# smd-proto.net
KiCad netlist of a schematic drawn in EAGLE
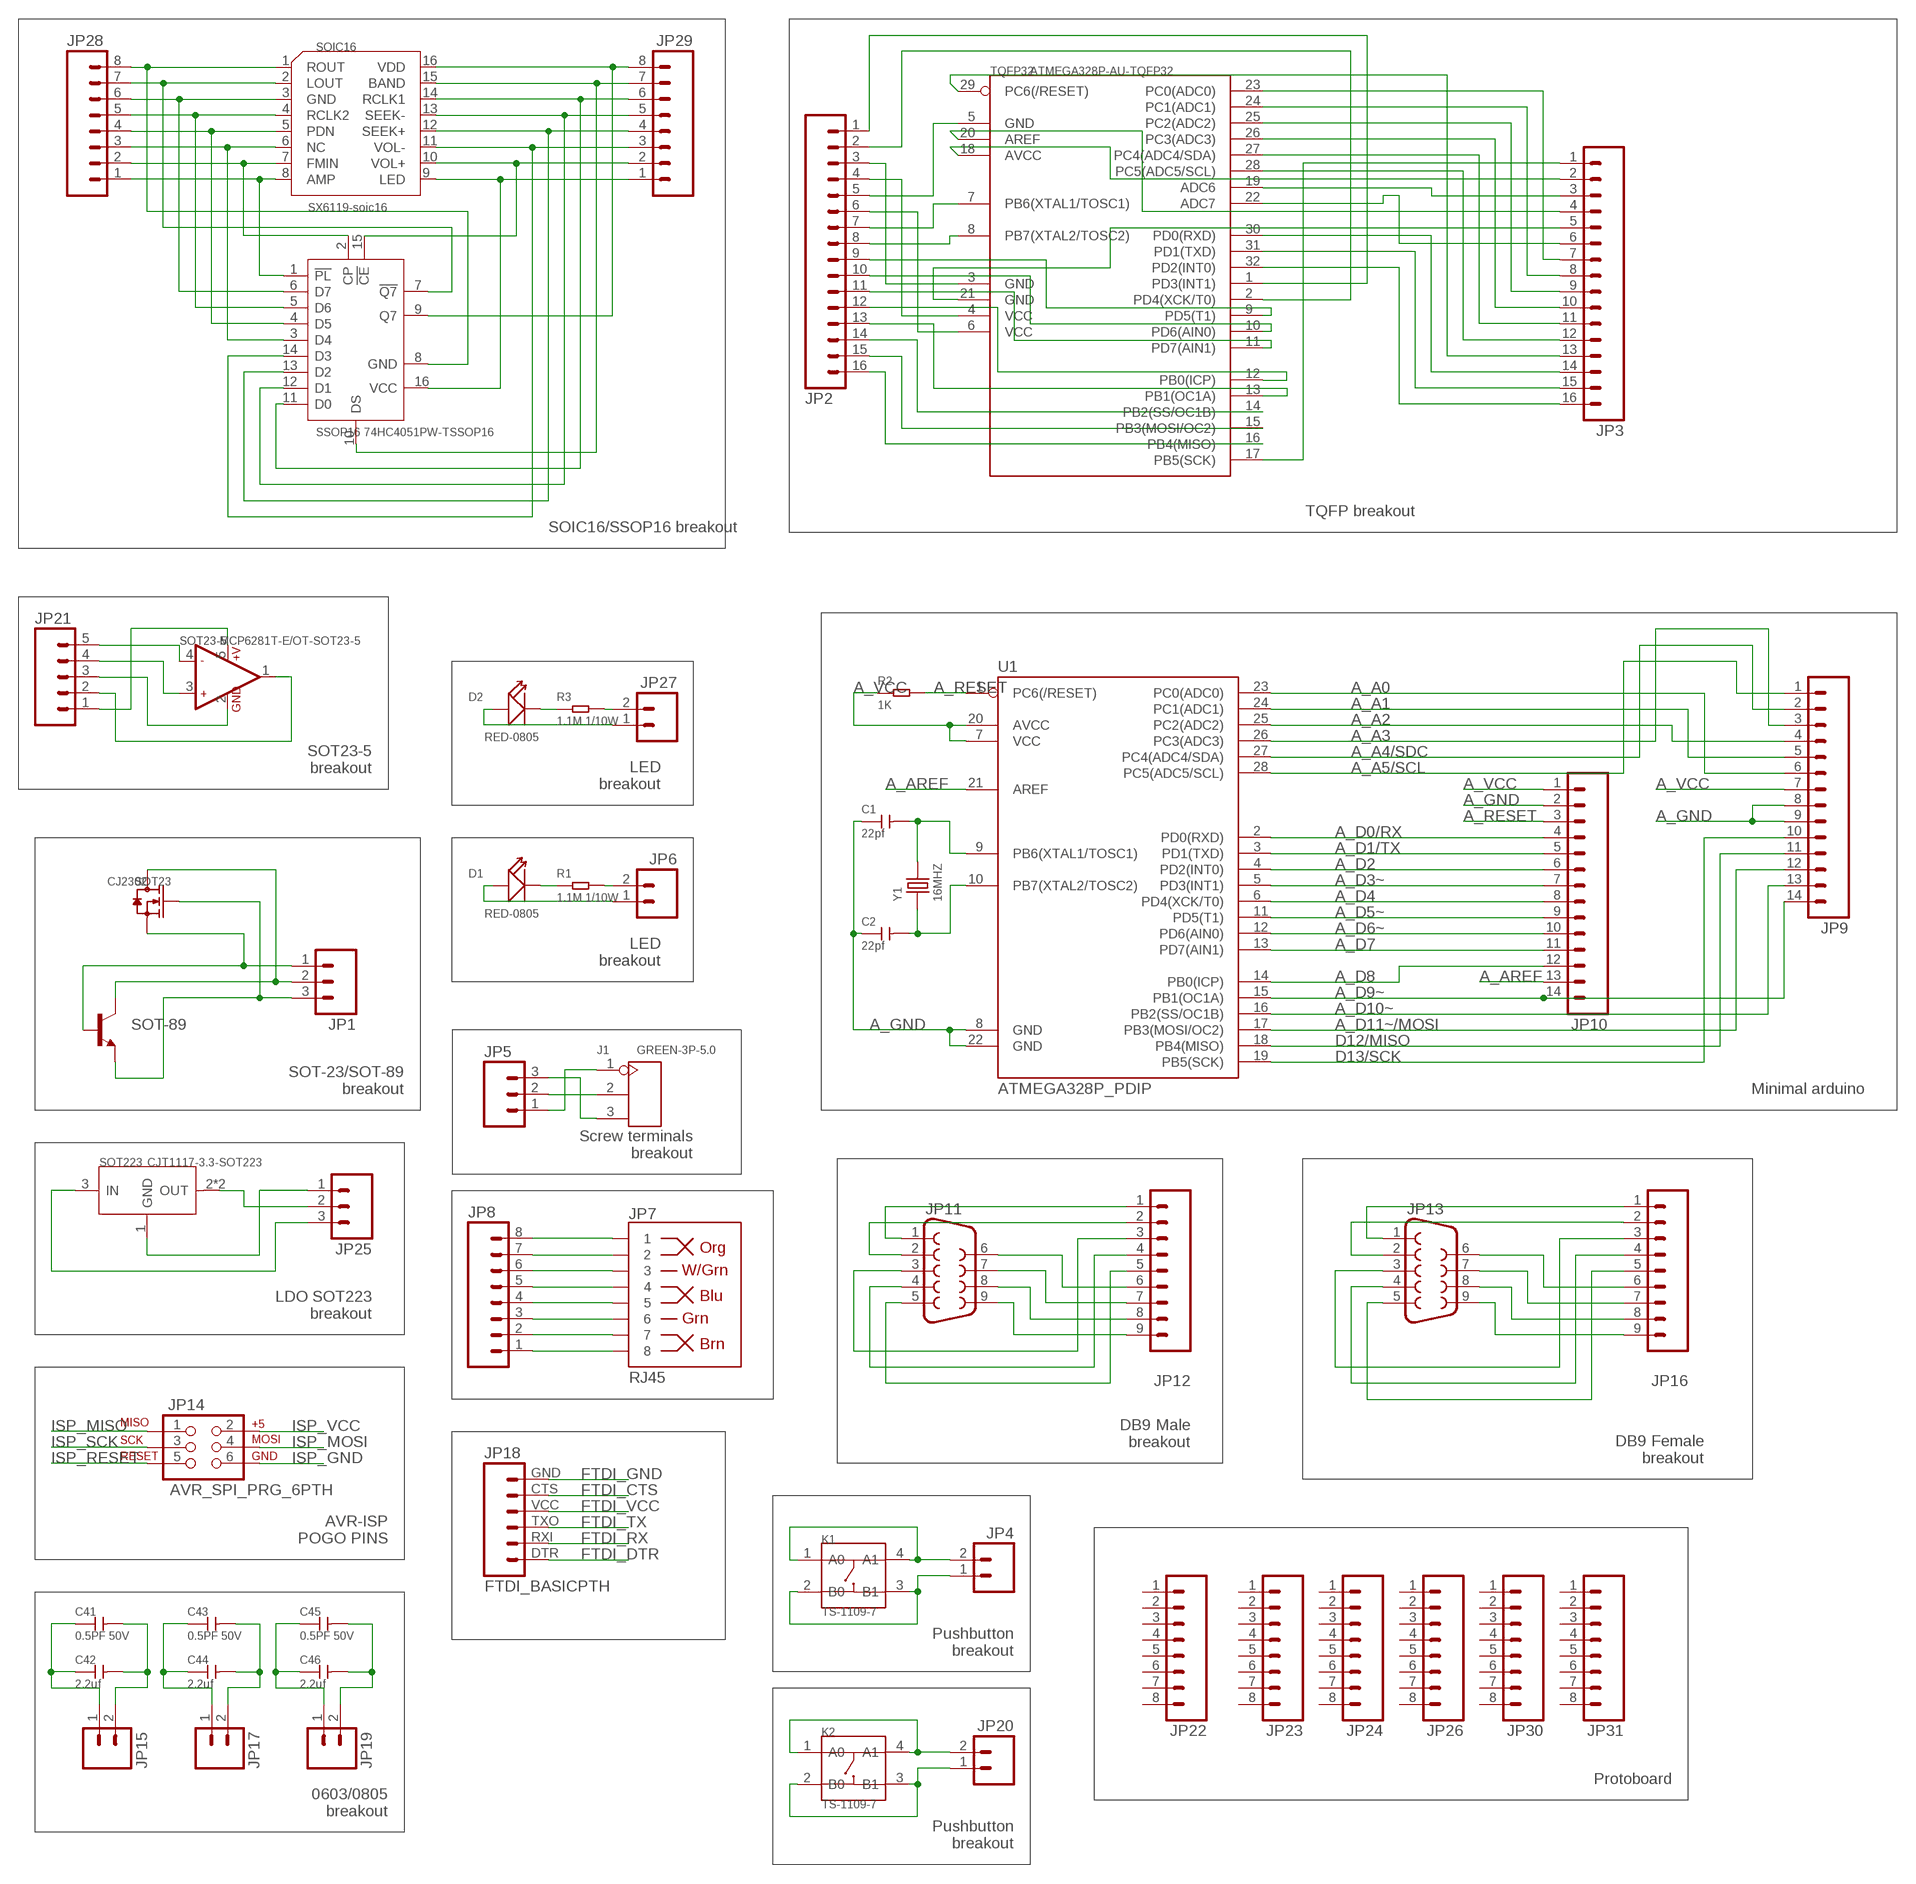
[diagram p0: schematic, sheet 1]

(export (version "E")
  (design (tool "Eeschema 10.0.6"))
  (components
    (comp (ref "C1")
      (value "22pf")
      (footprint "eagle-import:C0603")
      (libsource (lib "eagle-import") (part "CERAMIC-22PF-50V-5%-NPO(0603)"))
    )
    (comp (ref "C2")
      (value "22pf")
      (footprint "eagle-import:C0603")
      (libsource (lib "eagle-import") (part "CERAMIC-22PF-50V-5%-NPO(0603)"))
    )
    (comp (ref "C41")
      (value "0.5PF 50V")
      (footprint "eagle-import:C0603")
      (libsource (lib "eagle-import") (part "CERAMIC-0.5PF-50V-0.1PF-NPO(0603)"))
    )
    (comp (ref "C42")
      (value "2.2uf")
      (footprint "eagle-import:C0805")
      (fields (field (name "MPN") "CC0805KKX7R8BB225"))
      (libsource (lib "eagle-import") (part "CERAMIC-2.2UF-25V-10%-X7R(0805)"))
    )
    (comp (ref "C43")
      (value "0.5PF 50V")
      (footprint "eagle-import:C0603")
      (libsource (lib "eagle-import") (part "CERAMIC-0.5PF-50V-0.1PF-NPO(0603)"))
    )
    (comp (ref "C44")
      (value "2.2uf")
      (footprint "eagle-import:C0805")
      (fields (field (name "MPN") "CC0805KKX7R8BB225"))
      (libsource (lib "eagle-import") (part "CERAMIC-2.2UF-25V-10%-X7R(0805)"))
    )
    (comp (ref "C45")
      (value "0.5PF 50V")
      (footprint "eagle-import:C0603")
      (libsource (lib "eagle-import") (part "CERAMIC-0.5PF-50V-0.1PF-NPO(0603)"))
    )
    (comp (ref "C46")
      (value "2.2uf")
      (footprint "eagle-import:C0805")
      (fields (field (name "MPN") "CC0805KKX7R8BB225"))
      (libsource (lib "eagle-import") (part "CERAMIC-2.2UF-25V-10%-X7R(0805)"))
    )
    (comp (ref "D1")
      (value "RED-0805")
      (footprint "eagle-import:LED-0805")
      (fields (field (name "MPN") "17-215SURC/S530-A2/TR8"))
      (libsource (lib "eagle-import") (part "SMD-LED-CLEAR-RED(0805)"))
    )
    (comp (ref "D2")
      (value "RED-0805")
      (footprint "eagle-import:LED-0805")
      (fields (field (name "MPN") "17-215SURC/S530-A2/TR8"))
      (libsource (lib "eagle-import") (part "SMD-LED-CLEAR-RED(0805)"))
    )
    (comp (ref "J1")
      (value "GREEN-3P-5.0")
      (footprint "eagle-import:H3-5.0-15.5X8.0MM")
      (libsource (lib "eagle-import") (part "SCREW-TERMINAL-GREEN(3P-5.0)"))
    )
    (comp (ref "JP1")
      (value "M03PTH")
      (footprint "eagle-import:1X03")
      (libsource (lib "eagle-import") (part "M03PTH"))
    )
    (comp (ref "JP2")
      (value "M16PTH")
      (footprint "eagle-import:1X16")
      (libsource (lib "eagle-import") (part "M16PTH"))
    )
    (comp (ref "JP3")
      (value "M16PTH")
      (footprint "eagle-import:1X16")
      (libsource (lib "eagle-import") (part "M16PTH"))
    )
    (comp (ref "JP4")
      (value "M02PTH")
      (footprint "eagle-import:1X02")
      (libsource (lib "eagle-import") (part "M02PTH"))
    )
    (comp (ref "JP5")
      (value "M03PTH")
      (footprint "eagle-import:1X03")
      (libsource (lib "eagle-import") (part "M03PTH"))
    )
    (comp (ref "JP6")
      (value "M02PTH")
      (footprint "eagle-import:1X02")
      (libsource (lib "eagle-import") (part "M02PTH"))
    )
    (comp (ref "JP7")
      (value "RJ45")
      (footprint "eagle-import:RJ45-8")
      (libsource (lib "eagle-import") (part "RJ45-8PTH"))
    )
    (comp (ref "JP8")
      (value "M08")
      (footprint "eagle-import:1X08_ROUND")
      (libsource (lib "eagle-import") (part "M08"))
    )
    (comp (ref "JP9")
      (value "M14")
      (footprint "eagle-import:1X14")
      (libsource (lib "eagle-import") (part "M14"))
    )
    (comp (ref "JP10")
      (value "M14")
      (footprint "eagle-import:1X14")
      (libsource (lib "eagle-import") (part "M14"))
    )
    (comp (ref "JP11")
      (value "DB9MALE")
      (footprint "eagle-import:DB9_MALE")
      (libsource (lib "eagle-import") (part "DB9MALE"))
    )
    (comp (ref "JP12")
      (value "M09")
      (footprint "eagle-import:1X09")
      (libsource (lib "eagle-import") (part "M09"))
    )
    (comp (ref "JP13")
      (value "DB9FEMALE")
      (footprint "eagle-import:DB9")
      (libsource (lib "eagle-import") (part "DB9FEMALE"))
    )
    (comp (ref "JP14")
      (value "AVR_SPI_PRG_6PTH")
      (footprint "eagle-import:2X3")
      (libsource (lib "eagle-import") (part "AVR_SPI_PRG_6PTH"))
    )
    (comp (ref "JP15")
      (value "M02PTH")
      (footprint "eagle-import:1X02")
      (libsource (lib "eagle-import") (part "M02PTH"))
    )
    (comp (ref "JP16")
      (value "M09")
      (footprint "eagle-import:1X09")
      (libsource (lib "eagle-import") (part "M09"))
    )
    (comp (ref "JP17")
      (value "M02PTH")
      (footprint "eagle-import:1X02")
      (libsource (lib "eagle-import") (part "M02PTH"))
    )
    (comp (ref "JP18")
      (value "FTDI_BASICPTH")
      (footprint "eagle-import:FTDI_BASIC")
      (libsource (lib "eagle-import") (part "FTDI_BASICPTH"))
    )
    (comp (ref "JP19")
      (value "M02PTH")
      (footprint "eagle-import:1X02")
      (libsource (lib "eagle-import") (part "M02PTH"))
    )
    (comp (ref "JP20")
      (value "M02PTH")
      (footprint "eagle-import:1X02")
      (libsource (lib "eagle-import") (part "M02PTH"))
    )
    (comp (ref "JP21")
      (value "M05PTH")
      (footprint "eagle-import:1X05")
      (libsource (lib "eagle-import") (part "M05PTH"))
    )
    (comp (ref "JP22")
      (value "M08NO_SILK_FEMALE_PTH")
      (footprint "eagle-import:1X08_NO_SILK")
      (libsource (lib "eagle-import") (part "M08NO_SILK_FEMALE_PTH"))
    )
    (comp (ref "JP23")
      (value "M08NO_SILK_FEMALE_PTH")
      (footprint "eagle-import:1X08_NO_SILK")
      (libsource (lib "eagle-import") (part "M08NO_SILK_FEMALE_PTH"))
    )
    (comp (ref "JP24")
      (value "M08NO_SILK_FEMALE_PTH")
      (footprint "eagle-import:1X08_NO_SILK")
      (libsource (lib "eagle-import") (part "M08NO_SILK_FEMALE_PTH"))
    )
    (comp (ref "JP25")
      (value "M03PTH")
      (footprint "eagle-import:1X03")
      (libsource (lib "eagle-import") (part "M03PTH"))
    )
    (comp (ref "JP26")
      (value "M08NO_SILK_FEMALE_PTH")
      (footprint "eagle-import:1X08_NO_SILK")
      (libsource (lib "eagle-import") (part "M08NO_SILK_FEMALE_PTH"))
    )
    (comp (ref "JP27")
      (value "M02PTH")
      (footprint "eagle-import:1X02")
      (libsource (lib "eagle-import") (part "M02PTH"))
    )
    (comp (ref "JP28")
      (value "M08")
      (footprint "eagle-import:1X08_ROUND")
      (libsource (lib "eagle-import") (part "M08"))
    )
    (comp (ref "JP29")
      (value "M08")
      (footprint "eagle-import:1X08_ROUND")
      (libsource (lib "eagle-import") (part "M08"))
    )
    (comp (ref "JP30")
      (value "M08NO_SILK_FEMALE_PTH")
      (footprint "eagle-import:1X08_NO_SILK")
      (libsource (lib "eagle-import") (part "M08NO_SILK_FEMALE_PTH"))
    )
    (comp (ref "JP31")
      (value "M08NO_SILK_FEMALE_PTH")
      (footprint "eagle-import:1X08_NO_SILK")
      (libsource (lib "eagle-import") (part "M08NO_SILK_FEMALE_PTH"))
    )
    (comp (ref "K1")
      (value "TS-1109-7")
      (footprint "eagle-import:SW4-6.2X6.2X5.0MM")
      (libsource (lib "eagle-import") (part "DIP-BUTTON-TOP-BLACK(4P-D6.2MM)"))
    )
    (comp (ref "K2")
      (value "TS-1109-7")
      (footprint "eagle-import:SW4-6.2X6.2X5.0MM")
      (libsource (lib "eagle-import") (part "DIP-BUTTON-TOP-BLACK(4P-D6.2MM)"))
    )
    (comp (ref "R1")
      (value "1.1M 1/10W")
      (footprint "eagle-import:R0603")
      (fields (field (name "MPN") "RC0603FR-071M1L"))
      (libsource (lib "eagle-import") (part "SMD-RES-1.1M-1%-1/10W(0603)"))
    )
    (comp (ref "R2")
      (value "1K")
      (footprint "eagle-import:R0603")
      (fields (field (name "MPN") "RC0603JR-075K6L"))
      (libsource (lib "eagle-import") (part "SMD-RES-5.6K-5%-1/10W(0603)"))
    )
    (comp (ref "R3")
      (value "1.1M 1/10W")
      (footprint "eagle-import:R0603")
      (fields (field (name "MPN") "RC0603FR-071M1L"))
      (libsource (lib "eagle-import") (part "SMD-RES-1.1M-1%-1/10W(0603)"))
    )
    (comp (ref "SOIC16")
      (value "SX6119-soic16")
      (footprint "eagle-import:SOIC16-1.27-10X3.9MM")
      (fields (field (name "MPN") "SX6119"))
      (libsource (lib "eagle-import") (part "AMPLIFIER-SX6119(SOIC16)"))
    )
    (comp (ref "SOT-89")
      (value "TRANSISTOR_NPNSOT89")
      (footprint "eagle-import:SOT89")
      (libsource (lib "eagle-import") (part "TRANSISTOR_NPNSOT89"))
    )
    (comp (ref "SOT23")
      (value "CJ2302")
      (footprint "eagle-import:SOT-23")
      (libsource (lib "eagle-import") (part "SMD-MOSFET-N-CH-20V-2.1A-CJ2302(SOT-23)"))
    )
    (comp (ref "SOT23-5")
      (value "MCP6281T-E/OT-SOT23-5")
      (footprint "eagle-import:SOT-23-5")
      (fields (field (name "MPN") "MCP6281T-E/OT"))
      (libsource (lib "eagle-import") (part "AMPLIFIER-MCP6281T-E/OT(SOT23-5)"))
    )
    (comp (ref "SOT223")
      (value "CJT1117-3.3-SOT223")
      (footprint "eagle-import:SOT-223")
      (fields (field (name "MPN") "CJT1117-3.3"))
      (libsource (lib "eagle-import") (part "PMIC-CJT1117-3.3(SOT223)"))
    )
    (comp (ref "SSOP16")
      (value "74HC4051PW-TSSOP16")
      (footprint "eagle-import:TSSOP16-0.65-5X4.4MM")
      (fields (field (name "MPN") "74HC4051PW"))
      (libsource (lib "eagle-import") (part "LOGIC-74HC4051PW(TSSOP16)"))
    )
    (comp (ref "TQFP32")
      (value "ATMEGA328P-AU-TQFP32")
      (footprint "eagle-import:TQFP32-0.8-7X7MM")
      (fields (field (name "MPN") "ATMEGA328P-AU"))
      (libsource (lib "eagle-import") (part "MCU-ATMEGA328P-AU(TQFP32)"))
    )
    (comp (ref "U1")
      (value "ATMEGA328P_PDIP")
      (footprint "eagle-import:DIL28-3")
      (libsource (lib "eagle-import") (part "ATMEGA328P_PDIP"))
    )
    (comp (ref "Y1")
      (value "16MHZ")
      (footprint "eagle-import:X2-SMD-5.0X3.2X1.3MM")
      (fields (field (name "MPN") "X053201602002"))
      (libsource (lib "eagle-import") (part "SMD-CRYSTAL-16MHZ-8PF-20PPM-40R(2P-5.0X3.2MM)"))
    )
  )
  (nets
    (net (code "1") (name "/A_A0") (class "Default")
      (node (ref "JP9") (pin "6") (pinfunction "6_6") (pintype "passive"))
      (node (ref "U1") (pin "23") (pinfunction "PC0(ADC0)_23") (pintype "bidirectional"))
    )
    (net (code "2") (name "/A_A1") (class "Default")
      (node (ref "JP9") (pin "5") (pinfunction "5_5") (pintype "passive"))
      (node (ref "U1") (pin "24") (pinfunction "PC1(ADC1)_24") (pintype "bidirectional"))
    )
    (net (code "3") (name "/A_A2") (class "Default")
      (node (ref "JP9") (pin "4") (pinfunction "4_4") (pintype "passive"))
      (node (ref "U1") (pin "25") (pinfunction "PC2(ADC2)_25") (pintype "bidirectional"))
    )
    (net (code "4") (name "/A_A3") (class "Default")
      (node (ref "JP9") (pin "3") (pinfunction "3_3") (pintype "passive"))
      (node (ref "U1") (pin "26") (pinfunction "PC3(ADC3)_26") (pintype "bidirectional"))
    )
    (net (code "5") (name "/A_A4{slash}SDC") (class "Default")
      (node (ref "JP9") (pin "2") (pinfunction "2_2") (pintype "passive"))
      (node (ref "U1") (pin "27") (pinfunction "PC4(ADC4/SDA)_27") (pintype "bidirectional"))
    )
    (net (code "6") (name "/A_A5{slash}SCL") (class "Default")
      (node (ref "JP9") (pin "1") (pinfunction "1_1") (pintype "passive"))
      (node (ref "U1") (pin "28") (pinfunction "PC5(ADC5/SCL)_28") (pintype "bidirectional"))
    )
    (net (code "7") (name "/A_AREF") (class "Default")
      (node (ref "JP10") (pin "13") (pinfunction "13_13") (pintype "passive"))
      (node (ref "U1") (pin "21") (pinfunction "AREF_21") (pintype "bidirectional"))
    )
    (net (code "8") (name "/A_D0{slash}RX") (class "Default")
      (node (ref "JP10") (pin "4") (pinfunction "4_4") (pintype "passive"))
      (node (ref "U1") (pin "2") (pinfunction "PD0(RXD)_2") (pintype "bidirectional"))
    )
    (net (code "9") (name "/A_D1{slash}TX") (class "Default")
      (node (ref "JP10") (pin "5") (pinfunction "5_5") (pintype "passive"))
      (node (ref "U1") (pin "3") (pinfunction "PD1(TXD)_3") (pintype "bidirectional"))
    )
    (net (code "10") (name "/A_D2") (class "Default")
      (node (ref "JP10") (pin "6") (pinfunction "6_6") (pintype "passive"))
      (node (ref "U1") (pin "4") (pinfunction "PD2(INT0)_4") (pintype "bidirectional"))
    )
    (net (code "11") (name "/A_D3~{}") (class "Default")
      (node (ref "JP10") (pin "7") (pinfunction "7_7") (pintype "passive"))
      (node (ref "U1") (pin "5") (pinfunction "PD3(INT1)_5") (pintype "bidirectional"))
    )
    (net (code "12") (name "/A_D4") (class "Default")
      (node (ref "JP10") (pin "8") (pinfunction "8_8") (pintype "passive"))
      (node (ref "U1") (pin "6") (pinfunction "PD4(XCK/T0)_6") (pintype "bidirectional"))
    )
    (net (code "13") (name "/A_D5~{}") (class "Default")
      (node (ref "JP10") (pin "9") (pinfunction "9_9") (pintype "passive"))
      (node (ref "U1") (pin "11") (pinfunction "PD5(T1)_11") (pintype "bidirectional"))
    )
    (net (code "14") (name "/A_D6~{}") (class "Default")
      (node (ref "JP10") (pin "10") (pinfunction "10_10") (pintype "passive"))
      (node (ref "U1") (pin "12") (pinfunction "PD6(AIN0)_12") (pintype "bidirectional"))
    )
    (net (code "15") (name "/A_D7") (class "Default")
      (node (ref "JP10") (pin "11") (pinfunction "11_11") (pintype "passive"))
      (node (ref "U1") (pin "13") (pinfunction "PD7(AIN1)_13") (pintype "bidirectional"))
    )
    (net (code "16") (name "/A_D8") (class "Default")
      (node (ref "JP10") (pin "12") (pinfunction "12_12") (pintype "passive"))
      (node (ref "U1") (pin "14") (pinfunction "PB0(ICP)_14") (pintype "bidirectional"))
    )
    (net (code "17") (name "/A_D9~{}") (class "Default")
      (node (ref "JP10") (pin "14") (pinfunction "14_14") (pintype "passive"))
      (node (ref "JP9") (pin "14") (pinfunction "14_14") (pintype "passive"))
      (node (ref "U1") (pin "15") (pinfunction "PB1(OC1A)_15") (pintype "bidirectional"))
    )
    (net (code "18") (name "/A_D10~{}") (class "Default")
      (node (ref "JP9") (pin "13") (pinfunction "13_13") (pintype "passive"))
      (node (ref "U1") (pin "16") (pinfunction "PB2(SS/OC1B)_16") (pintype "bidirectional"))
    )
    (net (code "19") (name "/A_D11~{{slash}MOSI}") (class "Default")
      (node (ref "JP9") (pin "12") (pinfunction "12_12") (pintype "passive"))
      (node (ref "U1") (pin "17") (pinfunction "PB3(MOSI/OC2)_17") (pintype "bidirectional"))
    )
    (net (code "20") (name "/A_GND") (class "Default")
      (node (ref "C1") (pin "1") (pinfunction "1_1") (pintype "passive"))
      (node (ref "C2") (pin "1") (pinfunction "1_1") (pintype "passive"))
      (node (ref "JP10") (pin "2") (pinfunction "2_2") (pintype "passive"))
      (node (ref "JP9") (pin "8") (pinfunction "8_8") (pintype "passive"))
      (node (ref "JP9") (pin "9") (pinfunction "9_9") (pintype "passive"))
      (node (ref "U1") (pin "22") (pinfunction "GND_22") (pintype "bidirectional"))
      (node (ref "U1") (pin "8") (pinfunction "GND_8") (pintype "bidirectional"))
    )
    (net (code "21") (name "/A_RESET") (class "Default")
      (node (ref "JP10") (pin "3") (pinfunction "3_3") (pintype "passive"))
      (node (ref "R2") (pin "2") (pinfunction "2_2") (pintype "passive"))
      (node (ref "U1") (pin "1") (pinfunction "PC6(/RESET)_1") (pintype "bidirectional"))
    )
    (net (code "22") (name "/A_VCC") (class "Default")
      (node (ref "JP10") (pin "1") (pinfunction "1_1") (pintype "passive"))
      (node (ref "JP9") (pin "7") (pinfunction "7_7") (pintype "passive"))
      (node (ref "R2") (pin "1") (pinfunction "1_1") (pintype "passive"))
      (node (ref "U1") (pin "20") (pinfunction "AVCC_20") (pintype "bidirectional"))
      (node (ref "U1") (pin "7") (pinfunction "VCC_7") (pintype "bidirectional"))
    )
    (net (code "23") (name "/D12{slash}MISO") (class "Default")
      (node (ref "JP9") (pin "11") (pinfunction "11_11") (pintype "passive"))
      (node (ref "U1") (pin "18") (pinfunction "PB4(MISO)_18") (pintype "bidirectional"))
    )
    (net (code "24") (name "/D13{slash}SCK") (class "Default")
      (node (ref "JP9") (pin "10") (pinfunction "10_10") (pintype "passive"))
      (node (ref "U1") (pin "19") (pinfunction "PB5(SCK)_19") (pintype "bidirectional"))
    )
    (net (code "25") (name "/FTDI_CTS") (class "Default")
      (node (ref "JP18") (pin "CTS") (pinfunction "5_CTS") (pintype "passive"))
    )
    (net (code "26") (name "/FTDI_DTR") (class "Default")
      (node (ref "JP18") (pin "DTR") (pinfunction "1_DTR") (pintype "passive"))
    )
    (net (code "27") (name "/FTDI_GND") (class "Default")
      (node (ref "JP18") (pin "GND") (pinfunction "6_GND") (pintype "passive"))
    )
    (net (code "28") (name "/FTDI_RX") (class "Default")
      (node (ref "JP18") (pin "RXI") (pinfunction "2_RXI") (pintype "passive"))
    )
    (net (code "29") (name "/FTDI_TX") (class "Default")
      (node (ref "JP18") (pin "TXO") (pinfunction "3_TXO") (pintype "passive"))
    )
    (net (code "30") (name "/FTDI_VCC") (class "Default")
      (node (ref "JP18") (pin "VCC") (pinfunction "4_VCC") (pintype "passive"))
    )
    (net (code "31") (name "/ISP_GND") (class "Default")
      (node (ref "JP14") (pin "6") (pinfunction "6_6") (pintype "passive"))
    )
    (net (code "32") (name "/ISP_MISO") (class "Default")
      (node (ref "JP14") (pin "1") (pinfunction "1_1") (pintype "passive"))
    )
    (net (code "33") (name "/ISP_MOSI") (class "Default")
      (node (ref "JP14") (pin "4") (pinfunction "4_4") (pintype "passive"))
    )
    (net (code "34") (name "/ISP_RESET") (class "Default")
      (node (ref "JP14") (pin "5") (pinfunction "5_5") (pintype "passive"))
    )
    (net (code "35") (name "/ISP_SCK") (class "Default")
      (node (ref "JP14") (pin "3") (pinfunction "3_3") (pintype "passive"))
    )
    (net (code "36") (name "/ISP_VCC") (class "Default")
      (node (ref "JP14") (pin "2") (pinfunction "2_2") (pintype "passive"))
    )
    (net (code "37") (name "Net-(C41-Pad1)") (class "Default")
      (node (ref "C41") (pin "1") (pinfunction "1_1") (pintype "passive"))
      (node (ref "C42") (pin "1") (pinfunction "1_1") (pintype "passive"))
      (node (ref "JP15") (pin "1") (pinfunction "1_1") (pintype "passive"))
    )
    (net (code "38") (name "Net-(C41-Pad2)") (class "Default")
      (node (ref "C41") (pin "2") (pinfunction "2_2") (pintype "passive"))
      (node (ref "C42") (pin "2") (pinfunction "2_2") (pintype "passive"))
      (node (ref "JP15") (pin "2") (pinfunction "2_2") (pintype "passive"))
    )
    (net (code "39") (name "Net-(C43-Pad1)") (class "Default")
      (node (ref "C43") (pin "1") (pinfunction "1_1") (pintype "passive"))
      (node (ref "C44") (pin "1") (pinfunction "1_1") (pintype "passive"))
      (node (ref "JP17") (pin "1") (pinfunction "1_1") (pintype "passive"))
    )
    (net (code "40") (name "Net-(C43-Pad2)") (class "Default")
      (node (ref "C43") (pin "2") (pinfunction "2_2") (pintype "passive"))
      (node (ref "C44") (pin "2") (pinfunction "2_2") (pintype "passive"))
      (node (ref "JP17") (pin "2") (pinfunction "2_2") (pintype "passive"))
    )
    (net (code "41") (name "Net-(C45-Pad1)") (class "Default")
      (node (ref "C45") (pin "1") (pinfunction "1_1") (pintype "passive"))
      (node (ref "C46") (pin "1") (pinfunction "1_1") (pintype "passive"))
      (node (ref "JP19") (pin "1") (pinfunction "1_1") (pintype "passive"))
    )
    (net (code "42") (name "Net-(C45-Pad2)") (class "Default")
      (node (ref "C45") (pin "2") (pinfunction "2_2") (pintype "passive"))
      (node (ref "C46") (pin "2") (pinfunction "2_2") (pintype "passive"))
      (node (ref "JP19") (pin "2") (pinfunction "2_2") (pintype "passive"))
    )
    (net (code "43") (name "Net-(D1-Pad+)") (class "Default")
      (node (ref "D1") (pin "+") (pinfunction "+_+") (pintype "passive"))
      (node (ref "JP6") (pin "1") (pinfunction "1_1") (pintype "passive"))
    )
    (net (code "44") (name "Net-(D1-Pad-)") (class "Default")
      (node (ref "D1") (pin "-") (pinfunction "-_-") (pintype "passive"))
      (node (ref "R1") (pin "1") (pinfunction "1_1") (pintype "passive"))
    )
    (net (code "45") (name "Net-(D2-Pad+)") (class "Default")
      (node (ref "D2") (pin "+") (pinfunction "+_+") (pintype "passive"))
      (node (ref "JP27") (pin "1") (pinfunction "1_1") (pintype "passive"))
    )
    (net (code "46") (name "Net-(D2-Pad-)") (class "Default")
      (node (ref "D2") (pin "-") (pinfunction "-_-") (pintype "passive"))
      (node (ref "R3") (pin "1") (pinfunction "1_1") (pintype "passive"))
    )
    (net (code "47") (name "Net-(J1-P$1)") (class "Default")
      (node (ref "J1") (pin "1") (pinfunction "P$1_1") (pintype "bidirectional"))
      (node (ref "JP5") (pin "1") (pinfunction "1_1") (pintype "passive"))
    )
    (net (code "48") (name "Net-(J1-P$2)") (class "Default")
      (node (ref "J1") (pin "2") (pinfunction "P$2_2") (pintype "bidirectional"))
      (node (ref "JP5") (pin "2") (pinfunction "2_2") (pintype "passive"))
    )
    (net (code "49") (name "Net-(J1-P$3)") (class "Default")
      (node (ref "J1") (pin "3") (pinfunction "P$3_3") (pintype "bidirectional"))
      (node (ref "JP5") (pin "3") (pinfunction "3_3") (pintype "passive"))
    )
    (net (code "50") (name "Net-(JP2-Pad3)") (class "Default")
      (node (ref "JP2") (pin "3") (pinfunction "3_3") (pintype "passive"))
      (node (ref "TQFP32") (pin "3") (pinfunction "GND_3") (pintype "bidirectional"))
    )
    (net (code "51") (name "Net-(JP2-Pad4)") (class "Default")
      (node (ref "JP2") (pin "4") (pinfunction "4_4") (pintype "passive"))
      (node (ref "TQFP32") (pin "4") (pinfunction "VCC_4") (pintype "bidirectional"))
    )
    (net (code "52") (name "Net-(JP2-Pad5)") (class "Default")
      (node (ref "JP2") (pin "5") (pinfunction "5_5") (pintype "passive"))
      (node (ref "TQFP32") (pin "5") (pinfunction "GND_5") (pintype "bidirectional"))
    )
    (net (code "53") (name "Net-(JP2-Pad6)") (class "Default")
      (node (ref "JP2") (pin "6") (pinfunction "6_6") (pintype "passive"))
      (node (ref "TQFP32") (pin "6") (pinfunction "VCC_6") (pintype "bidirectional"))
    )
    (net (code "54") (name "Net-(JP3-Pad5)") (class "Default")
      (node (ref "JP3") (pin "5") (pinfunction "5_5") (pintype "passive"))
      (node (ref "TQFP32") (pin "21") (pinfunction "GND_21") (pintype "bidirectional"))
    )
    (net (code "55") (name "Net-(JP6-Pad2)") (class "Default")
      (node (ref "JP6") (pin "2") (pinfunction "2_2") (pintype "passive"))
      (node (ref "R1") (pin "2") (pinfunction "2_2") (pintype "passive"))
    )
    (net (code "56") (name "Net-(JP7-Pad1)") (class "Default")
      (node (ref "JP7") (pin "1") (pinfunction "1_1") (pintype "bidirectional"))
      (node (ref "JP8") (pin "8") (pinfunction "8_8") (pintype "passive"))
    )
    (net (code "57") (name "Net-(JP7-Pad2)") (class "Default")
      (node (ref "JP7") (pin "2") (pinfunction "2_2") (pintype "bidirectional"))
      (node (ref "JP8") (pin "7") (pinfunction "7_7") (pintype "passive"))
    )
    (net (code "58") (name "Net-(JP7-Pad3)") (class "Default")
      (node (ref "JP7") (pin "3") (pinfunction "3_3") (pintype "bidirectional"))
      (node (ref "JP8") (pin "6") (pinfunction "6_6") (pintype "passive"))
    )
    (net (code "59") (name "Net-(JP7-Pad4)") (class "Default")
      (node (ref "JP7") (pin "4") (pinfunction "4_4") (pintype "bidirectional"))
      (node (ref "JP8") (pin "5") (pinfunction "5_5") (pintype "passive"))
    )
    (net (code "60") (name "Net-(JP7-Pad5)") (class "Default")
      (node (ref "JP7") (pin "5") (pinfunction "5_5") (pintype "bidirectional"))
      (node (ref "JP8") (pin "4") (pinfunction "4_4") (pintype "passive"))
    )
    (net (code "61") (name "Net-(JP7-Pad6)") (class "Default")
      (node (ref "JP7") (pin "6") (pinfunction "6_6") (pintype "bidirectional"))
      (node (ref "JP8") (pin "3") (pinfunction "3_3") (pintype "passive"))
    )
    (net (code "62") (name "Net-(JP7-Pad7)") (class "Default")
      (node (ref "JP7") (pin "7") (pinfunction "7_7") (pintype "bidirectional"))
      (node (ref "JP8") (pin "2") (pinfunction "2_2") (pintype "passive"))
    )
    (net (code "63") (name "Net-(JP7-Pad8)") (class "Default")
      (node (ref "JP7") (pin "8") (pinfunction "8_8") (pintype "bidirectional"))
      (node (ref "JP8") (pin "1") (pinfunction "1_1") (pintype "passive"))
    )
    (net (code "64") (name "Net-(JP11-Pad1)") (class "Default")
      (node (ref "JP11") (pin "1") (pinfunction "1_1") (pintype "passive"))
      (node (ref "JP12") (pin "1") (pinfunction "1_1") (pintype "passive"))
    )
    (net (code "65") (name "Net-(JP11-Pad2)") (class "Default")
      (node (ref "JP11") (pin "2") (pinfunction "2_2") (pintype "passive"))
      (node (ref "JP12") (pin "2") (pinfunction "2_2") (pintype "passive"))
    )
    (net (code "66") (name "Net-(JP11-Pad3)") (class "Default")
      (node (ref "JP11") (pin "3") (pinfunction "3_3") (pintype "passive"))
      (node (ref "JP12") (pin "3") (pinfunction "3_3") (pintype "passive"))
    )
    (net (code "67") (name "Net-(JP11-Pad4)") (class "Default")
      (node (ref "JP11") (pin "4") (pinfunction "4_4") (pintype "passive"))
      (node (ref "JP12") (pin "4") (pinfunction "4_4") (pintype "passive"))
    )
    (net (code "68") (name "Net-(JP11-Pad5)") (class "Default")
      (node (ref "JP11") (pin "5") (pinfunction "5_5") (pintype "passive"))
      (node (ref "JP12") (pin "5") (pinfunction "5_5") (pintype "passive"))
    )
    (net (code "69") (name "Net-(JP11-Pad6)") (class "Default")
      (node (ref "JP11") (pin "6") (pinfunction "6_6") (pintype "passive"))
      (node (ref "JP12") (pin "6") (pinfunction "6_6") (pintype "passive"))
    )
    (net (code "70") (name "Net-(JP11-Pad7)") (class "Default")
      (node (ref "JP11") (pin "7") (pinfunction "7_7") (pintype "passive"))
      (node (ref "JP12") (pin "7") (pinfunction "7_7") (pintype "passive"))
    )
    (net (code "71") (name "Net-(JP11-Pad8)") (class "Default")
      (node (ref "JP11") (pin "8") (pinfunction "8_8") (pintype "passive"))
      (node (ref "JP12") (pin "8") (pinfunction "8_8") (pintype "passive"))
    )
    (net (code "72") (name "Net-(JP11-Pad9)") (class "Default")
      (node (ref "JP11") (pin "9") (pinfunction "9_9") (pintype "passive"))
      (node (ref "JP12") (pin "9") (pinfunction "9_9") (pintype "passive"))
    )
    (net (code "73") (name "Net-(JP13-Pad1)") (class "Default")
      (node (ref "JP13") (pin "1") (pinfunction "1_1") (pintype "passive"))
      (node (ref "JP16") (pin "1") (pinfunction "1_1") (pintype "passive"))
    )
    (net (code "74") (name "Net-(JP13-Pad2)") (class "Default")
      (node (ref "JP13") (pin "2") (pinfunction "2_2") (pintype "passive"))
      (node (ref "JP16") (pin "2") (pinfunction "2_2") (pintype "passive"))
    )
    (net (code "75") (name "Net-(JP13-Pad3)") (class "Default")
      (node (ref "JP13") (pin "3") (pinfunction "3_3") (pintype "passive"))
      (node (ref "JP16") (pin "3") (pinfunction "3_3") (pintype "passive"))
    )
    (net (code "76") (name "Net-(JP13-Pad4)") (class "Default")
      (node (ref "JP13") (pin "4") (pinfunction "4_4") (pintype "passive"))
      (node (ref "JP16") (pin "4") (pinfunction "4_4") (pintype "passive"))
    )
    (net (code "77") (name "Net-(JP13-Pad5)") (class "Default")
      (node (ref "JP13") (pin "5") (pinfunction "5_5") (pintype "passive"))
      (node (ref "JP16") (pin "5") (pinfunction "5_5") (pintype "passive"))
    )
    (net (code "78") (name "Net-(JP13-Pad6)") (class "Default")
      (node (ref "JP13") (pin "6") (pinfunction "6_6") (pintype "passive"))
      (node (ref "JP16") (pin "6") (pinfunction "6_6") (pintype "passive"))
    )
    (net (code "79") (name "Net-(JP13-Pad7)") (class "Default")
      (node (ref "JP13") (pin "7") (pinfunction "7_7") (pintype "passive"))
      (node (ref "JP16") (pin "7") (pinfunction "7_7") (pintype "passive"))
    )
    (net (code "80") (name "Net-(JP13-Pad8)") (class "Default")
      (node (ref "JP13") (pin "8") (pinfunction "8_8") (pintype "passive"))
      (node (ref "JP16") (pin "8") (pinfunction "8_8") (pintype "passive"))
    )
    (net (code "81") (name "Net-(JP13-Pad9)") (class "Default")
      (node (ref "JP13") (pin "9") (pinfunction "9_9") (pintype "passive"))
      (node (ref "JP16") (pin "9") (pinfunction "9_9") (pintype "passive"))
    )
    (net (code "82") (name "Net-(JP25-Pad2)") (class "Default")
      (node (ref "JP25") (pin "2") (pinfunction "2_2") (pintype "passive"))
      (node (ref "SOT223") (pin "2") (pinfunction "OUT_2") (pintype "bidirectional"))
      (node (ref "SOT223") (pin "TER") (pinfunction "OUT_TER") (pintype "bidirectional"))
    )
    (net (code "83") (name "Net-(JP27-Pad2)") (class "Default")
      (node (ref "JP27") (pin "2") (pinfunction "2_2") (pintype "passive"))
      (node (ref "R3") (pin "2") (pinfunction "2_2") (pintype "passive"))
    )
    (net (code "84") (name "Net-(K1-A0)") (class "Default")
      (node (ref "JP4") (pin "2") (pinfunction "2_2") (pintype "passive"))
      (node (ref "K1") (pin "1") (pinfunction "A0_1") (pintype "bidirectional"))
      (node (ref "K1") (pin "4") (pinfunction "A1_4") (pintype "bidirectional"))
    )
    (net (code "85") (name "Net-(K1-B0)") (class "Default")
      (node (ref "JP4") (pin "1") (pinfunction "1_1") (pintype "passive"))
      (node (ref "K1") (pin "2") (pinfunction "B0_2") (pintype "bidirectional"))
      (node (ref "K1") (pin "3") (pinfunction "B1_3") (pintype "bidirectional"))
    )
    (net (code "86") (name "Net-(K2-A0)") (class "Default")
      (node (ref "JP20") (pin "2") (pinfunction "2_2") (pintype "passive"))
      (node (ref "K2") (pin "1") (pinfunction "A0_1") (pintype "bidirectional"))
      (node (ref "K2") (pin "4") (pinfunction "A1_4") (pintype "bidirectional"))
    )
    (net (code "87") (name "Net-(K2-B0)") (class "Default")
      (node (ref "JP20") (pin "1") (pinfunction "1_1") (pintype "passive"))
      (node (ref "K2") (pin "2") (pinfunction "B0_2") (pintype "bidirectional"))
      (node (ref "K2") (pin "3") (pinfunction "B1_3") (pintype "bidirectional"))
    )
    (net (code "88") (name "Net-(SOIC16-AMP)") (class "Default")
      (node (ref "JP28") (pin "1") (pinfunction "1_1") (pintype "passive"))
      (node (ref "SOIC16") (pin "8") (pinfunction "AMP_8") (pintype "bidirectional"))
      (node (ref "SSOP16") (pin "1") (pinfunction "~{PL}_1") (pintype "input"))
    )
    (net (code "89") (name "Net-(SOIC16-BAND)") (class "Default")
      (node (ref "JP29") (pin "7") (pinfunction "7_7") (pintype "passive"))
      (node (ref "SOIC16") (pin "15") (pinfunction "BAND_15") (pintype "bidirectional"))
      (node (ref "SSOP16") (pin "10") (pinfunction "DS_10") (pintype "input"))
    )
    (net (code "90") (name "Net-(SOIC16-FMIN)") (class "Default")
      (node (ref "JP28") (pin "2") (pinfunction "2_2") (pintype "passive"))
      (node (ref "SOIC16") (pin "7") (pinfunction "FMIN_7") (pintype "bidirectional"))
      (node (ref "SSOP16") (pin "2") (pinfunction "CP_2") (pintype "input"))
    )
    (net (code "91") (name "Net-(SOIC16-GND)") (class "Default")
      (node (ref "JP28") (pin "6") (pinfunction "6_6") (pintype "passive"))
      (node (ref "SOIC16") (pin "3") (pinfunction "GND_3") (pintype "bidirectional"))
      (node (ref "SSOP16") (pin "6") (pinfunction "D7_6") (pintype "bidirectional"))
    )
    (net (code "92") (name "Net-(SOIC16-LED)") (class "Default")
      (node (ref "JP29") (pin "1") (pinfunction "1_1") (pintype "passive"))
      (node (ref "SOIC16") (pin "9") (pinfunction "LED_9") (pintype "bidirectional"))
      (node (ref "SSOP16") (pin "16") (pinfunction "VCC_16") (pintype "power_in"))
    )
    (net (code "93") (name "Net-(SOIC16-LOUT)") (class "Default")
      (node (ref "JP28") (pin "7") (pinfunction "7_7") (pintype "passive"))
      (node (ref "SOIC16") (pin "2") (pinfunction "LOUT_2") (pintype "bidirectional"))
      (node (ref "SSOP16") (pin "7") (pinfunction "~{Q7}_7") (pintype "bidirectional"))
    )
    (net (code "94") (name "Net-(SOIC16-NC)") (class "Default")
      (node (ref "JP28") (pin "3") (pinfunction "3_3") (pintype "passive"))
      (node (ref "SOIC16") (pin "6") (pinfunction "NC_6") (pintype "bidirectional"))
      (node (ref "SSOP16") (pin "3") (pinfunction "D4_3") (pintype "bidirectional"))
    )
    (net (code "95") (name "Net-(SOIC16-PDN)") (class "Default")
      (node (ref "JP28") (pin "4") (pinfunction "4_4") (pintype "passive"))
      (node (ref "SOIC16") (pin "5") (pinfunction "PDN_5") (pintype "bidirectional"))
      (node (ref "SSOP16") (pin "4") (pinfunction "D5_4") (pintype "bidirectional"))
    )
    (net (code "96") (name "Net-(SOIC16-RCLK1)") (class "Default")
      (node (ref "JP29") (pin "6") (pinfunction "6_6") (pintype "passive"))
      (node (ref "SOIC16") (pin "14") (pinfunction "RCLK1_14") (pintype "bidirectional"))
      (node (ref "SSOP16") (pin "11") (pinfunction "D0_11") (pintype "bidirectional"))
    )
    (net (code "97") (name "Net-(SOIC16-RCLK2)") (class "Default")
      (node (ref "JP28") (pin "5") (pinfunction "5_5") (pintype "passive"))
      (node (ref "SOIC16") (pin "4") (pinfunction "RCLK2_4") (pintype "bidirectional"))
      (node (ref "SSOP16") (pin "5") (pinfunction "D6_5") (pintype "bidirectional"))
    )
    (net (code "98") (name "Net-(SOIC16-ROUT)") (class "Default")
      (node (ref "JP28") (pin "8") (pinfunction "8_8") (pintype "passive"))
      (node (ref "SOIC16") (pin "1") (pinfunction "ROUT_1") (pintype "bidirectional"))
      (node (ref "SSOP16") (pin "8") (pinfunction "GND_8") (pintype "power_in"))
    )
    (net (code "99") (name "Net-(SOIC16-SEEK+)") (class "Default")
      (node (ref "JP29") (pin "4") (pinfunction "4_4") (pintype "passive"))
      (node (ref "SOIC16") (pin "12") (pinfunction "SEEK+_12") (pintype "bidirectional"))
      (node (ref "SSOP16") (pin "13") (pinfunction "D2_13") (pintype "bidirectional"))
    )
    (net (code "100") (name "Net-(SOIC16-SEEK-)") (class "Default")
      (node (ref "JP29") (pin "5") (pinfunction "5_5") (pintype "passive"))
      (node (ref "SOIC16") (pin "13") (pinfunction "SEEK-_13") (pintype "bidirectional"))
      (node (ref "SSOP16") (pin "12") (pinfunction "D1_12") (pintype "bidirectional"))
    )
    (net (code "101") (name "Net-(SOIC16-VDD)") (class "Default")
      (node (ref "JP29") (pin "8") (pinfunction "8_8") (pintype "passive"))
      (node (ref "SOIC16") (pin "16") (pinfunction "VDD_16") (pintype "bidirectional"))
      (node (ref "SSOP16") (pin "9") (pinfunction "Q7_9") (pintype "bidirectional"))
    )
    (net (code "102") (name "Net-(SOIC16-VOL+)") (class "Default")
      (node (ref "JP29") (pin "2") (pinfunction "2_2") (pintype "passive"))
      (node (ref "SOIC16") (pin "10") (pinfunction "VOL+_10") (pintype "bidirectional"))
      (node (ref "SSOP16") (pin "15") (pinfunction "~{CE}_15") (pintype "input"))
    )
    (net (code "103") (name "Net-(SOIC16-VOL-)") (class "Default")
      (node (ref "JP29") (pin "3") (pinfunction "3_3") (pintype "passive"))
      (node (ref "SOIC16") (pin "11") (pinfunction "VOL-_11") (pintype "bidirectional"))
      (node (ref "SSOP16") (pin "14") (pinfunction "D3_14") (pintype "bidirectional"))
    )
    (net (code "104") (name "Net-(SOT-89-B)") (class "Default")
      (node (ref "JP1") (pin "1") (pinfunction "1_1") (pintype "passive"))
      (node (ref "SOT-89") (pin "1") (pinfunction "B_1") (pintype "passive"))
      (node (ref "SOT23") (pin "2") (pinfunction "S_2") (pintype "passive"))
    )
    (net (code "105") (name "Net-(SOT-89-C)") (class "Default")
      (node (ref "JP1") (pin "2") (pinfunction "2_2") (pintype "passive"))
      (node (ref "SOT-89") (pin "2") (pinfunction "C_2") (pintype "passive"))
      (node (ref "SOT23") (pin "3") (pinfunction "D_3") (pintype "passive"))
    )
    (net (code "106") (name "Net-(SOT-89-E)") (class "Default")
      (node (ref "JP1") (pin "3") (pinfunction "3_3") (pintype "passive"))
      (node (ref "SOT-89") (pin "3") (pinfunction "E_3") (pintype "passive"))
      (node (ref "SOT23") (pin "1") (pinfunction "G_1") (pintype "passive"))
    )
    (net (code "107") (name "Net-(SOT23-5-+IN1)") (class "Default")
      (node (ref "JP21") (pin "4") (pinfunction "4_4") (pintype "passive"))
      (node (ref "SOT23-5") (pin "3") (pinfunction "+IN1_3") (pintype "input"))
    )
    (net (code "108") (name "Net-(SOT23-5-+V)") (class "Default")
      (node (ref "JP21") (pin "1") (pinfunction "1_1") (pintype "passive"))
      (node (ref "SOT23-5") (pin "5") (pinfunction "+V_5") (pintype "power_in"))
    )
    (net (code "109") (name "Net-(SOT23-5--IN1)") (class "Default")
      (node (ref "JP21") (pin "5") (pinfunction "5_5") (pintype "passive"))
      (node (ref "SOT23-5") (pin "4") (pinfunction "-IN1_4") (pintype "input"))
    )
    (net (code "110") (name "Net-(SOT23-5-GND)") (class "Default")
      (node (ref "JP21") (pin "3") (pinfunction "3_3") (pintype "passive"))
      (node (ref "SOT23-5") (pin "2") (pinfunction "GND_2") (pintype "power_in"))
    )
    (net (code "111") (name "Net-(SOT23-5-OUT1)") (class "Default")
      (node (ref "JP21") (pin "2") (pinfunction "2_2") (pintype "passive"))
      (node (ref "SOT23-5") (pin "1") (pinfunction "OUT1_1") (pintype "output"))
    )
    (net (code "112") (name "Net-(SOT223-GND)") (class "Default")
      (node (ref "JP25") (pin "1") (pinfunction "1_1") (pintype "passive"))
      (node (ref "SOT223") (pin "1") (pinfunction "GND_1") (pintype "bidirectional"))
    )
    (net (code "113") (name "Net-(SOT223-IN)") (class "Default")
      (node (ref "JP25") (pin "3") (pinfunction "3_3") (pintype "passive"))
      (node (ref "SOT223") (pin "3") (pinfunction "IN_3") (pintype "bidirectional"))
    )
    (net (code "114") (name "Net-(TQFP32-ADC6)") (class "Default")
      (node (ref "JP3") (pin "3") (pinfunction "3_3") (pintype "passive"))
      (node (ref "TQFP32") (pin "19") (pinfunction "ADC6_19") (pintype "bidirectional"))
    )
    (net (code "115") (name "Net-(TQFP32-ADC7)") (class "Default")
      (node (ref "JP3") (pin "6") (pinfunction "6_6") (pintype "passive"))
      (node (ref "TQFP32") (pin "22") (pinfunction "ADC7_22") (pintype "bidirectional"))
    )
    (net (code "116") (name "Net-(TQFP32-AREF)") (class "Default")
      (node (ref "JP3") (pin "4") (pinfunction "4_4") (pintype "passive"))
      (node (ref "TQFP32") (pin "20") (pinfunction "AREF_20") (pintype "bidirectional"))
    )
    (net (code "117") (name "Net-(TQFP32-AVCC)") (class "Default")
      (node (ref "JP3") (pin "2") (pinfunction "2_2") (pintype "passive"))
      (node (ref "TQFP32") (pin "18") (pinfunction "AVCC_18") (pintype "bidirectional"))
    )
    (net (code "118") (name "Net-(TQFP32-PB0(ICP))") (class "Default")
      (node (ref "JP2") (pin "12") (pinfunction "12_12") (pintype "passive"))
      (node (ref "TQFP32") (pin "12") (pinfunction "PB0(ICP)_12") (pintype "bidirectional"))
    )
    (net (code "119") (name "Net-(TQFP32-PB1(OC1A))") (class "Default")
      (node (ref "JP2") (pin "13") (pinfunction "13_13") (pintype "passive"))
      (node (ref "TQFP32") (pin "13") (pinfunction "PB1(OC1A)_13") (pintype "bidirectional"))
    )
    (net (code "120") (name "Net-(TQFP32-PB2(SS{slash}OC1B))") (class "Default")
      (node (ref "JP2") (pin "14") (pinfunction "14_14") (pintype "passive"))
      (node (ref "TQFP32") (pin "14") (pinfunction "PB2(SS/OC1B)_14") (pintype "bidirectional"))
    )
    (net (code "121") (name "Net-(TQFP32-PB3(MOSI{slash}OC2))") (class "Default")
      (node (ref "JP2") (pin "15") (pinfunction "15_15") (pintype "passive"))
      (node (ref "TQFP32") (pin "15") (pinfunction "PB3(MOSI/OC2)_15") (pintype "bidirectional"))
    )
    (net (code "122") (name "Net-(TQFP32-PB4(MISO))") (class "Default")
      (node (ref "JP2") (pin "16") (pinfunction "16_16") (pintype "passive"))
      (node (ref "TQFP32") (pin "16") (pinfunction "PB4(MISO)_16") (pintype "bidirectional"))
    )
    (net (code "123") (name "Net-(TQFP32-PB5(SCK))") (class "Default")
      (node (ref "JP3") (pin "1") (pinfunction "1_1") (pintype "passive"))
      (node (ref "TQFP32") (pin "17") (pinfunction "PB5(SCK)_17") (pintype "bidirectional"))
    )
    (net (code "124") (name "Net-(TQFP32-PB6(XTAL1{slash}TOSC1))") (class "Default")
      (node (ref "JP2") (pin "7") (pinfunction "7_7") (pintype "passive"))
      (node (ref "TQFP32") (pin "7") (pinfunction "PB6(XTAL1/TOSC1)_7") (pintype "bidirectional"))
    )
    (net (code "125") (name "Net-(TQFP32-PB7(XTAL2{slash}TOSC2))") (class "Default")
      (node (ref "JP2") (pin "8") (pinfunction "8_8") (pintype "passive"))
      (node (ref "TQFP32") (pin "8") (pinfunction "PB7(XTAL2/TOSC2)_8") (pintype "bidirectional"))
    )
    (net (code "126") (name "Net-(TQFP32-PC0(ADC0))") (class "Default")
      (node (ref "JP3") (pin "7") (pinfunction "7_7") (pintype "passive"))
      (node (ref "TQFP32") (pin "23") (pinfunction "PC0(ADC0)_23") (pintype "bidirectional"))
    )
    (net (code "127") (name "Net-(TQFP32-PC1(ADC1))") (class "Default")
      (node (ref "JP3") (pin "8") (pinfunction "8_8") (pintype "passive"))
      (node (ref "TQFP32") (pin "24") (pinfunction "PC1(ADC1)_24") (pintype "bidirectional"))
    )
    (net (code "128") (name "Net-(TQFP32-PC2(ADC2))") (class "Default")
      (node (ref "JP3") (pin "9") (pinfunction "9_9") (pintype "passive"))
      (node (ref "TQFP32") (pin "25") (pinfunction "PC2(ADC2)_25") (pintype "bidirectional"))
    )
    (net (code "129") (name "Net-(TQFP32-PC3(ADC3))") (class "Default")
      (node (ref "JP3") (pin "10") (pinfunction "10_10") (pintype "passive"))
      (node (ref "TQFP32") (pin "26") (pinfunction "PC3(ADC3)_26") (pintype "bidirectional"))
    )
    (net (code "130") (name "Net-(TQFP32-PC4(ADC4{slash}SDA))") (class "Default")
      (node (ref "JP3") (pin "11") (pinfunction "11_11") (pintype "passive"))
      (node (ref "TQFP32") (pin "27") (pinfunction "PC4(ADC4/SDA)_27") (pintype "bidirectional"))
    )
    (net (code "131") (name "Net-(TQFP32-PC5(ADC5{slash}SCL))") (class "Default")
      (node (ref "JP3") (pin "12") (pinfunction "12_12") (pintype "passive"))
      (node (ref "TQFP32") (pin "28") (pinfunction "PC5(ADC5/SCL)_28") (pintype "bidirectional"))
    )
    (net (code "132") (name "Net-(TQFP32-PC6({slash}RESET))") (class "Default")
      (node (ref "JP3") (pin "13") (pinfunction "13_13") (pintype "passive"))
      (node (ref "TQFP32") (pin "29") (pinfunction "PC6(/RESET)_29") (pintype "bidirectional"))
    )
    (net (code "133") (name "Net-(TQFP32-PD0(RXD))") (class "Default")
      (node (ref "JP3") (pin "14") (pinfunction "14_14") (pintype "passive"))
      (node (ref "TQFP32") (pin "30") (pinfunction "PD0(RXD)_30") (pintype "bidirectional"))
    )
    (net (code "134") (name "Net-(TQFP32-PD1(TXD))") (class "Default")
      (node (ref "JP3") (pin "15") (pinfunction "15_15") (pintype "passive"))
      (node (ref "TQFP32") (pin "31") (pinfunction "PD1(TXD)_31") (pintype "bidirectional"))
    )
    (net (code "135") (name "Net-(TQFP32-PD2(INT0))") (class "Default")
      (node (ref "JP3") (pin "16") (pinfunction "16_16") (pintype "passive"))
      (node (ref "TQFP32") (pin "32") (pinfunction "PD2(INT0)_32") (pintype "bidirectional"))
    )
    (net (code "136") (name "Net-(TQFP32-PD3(INT1))") (class "Default")
      (node (ref "JP2") (pin "1") (pinfunction "1_1") (pintype "passive"))
      (node (ref "TQFP32") (pin "1") (pinfunction "PD3(INT1)_1") (pintype "bidirectional"))
    )
    (net (code "137") (name "Net-(TQFP32-PD4(XCK{slash}T0))") (class "Default")
      (node (ref "JP2") (pin "2") (pinfunction "2_2") (pintype "passive"))
      (node (ref "TQFP32") (pin "2") (pinfunction "PD4(XCK/T0)_2") (pintype "bidirectional"))
    )
    (net (code "138") (name "Net-(TQFP32-PD5(T1))") (class "Default")
      (node (ref "JP2") (pin "9") (pinfunction "9_9") (pintype "passive"))
      (node (ref "TQFP32") (pin "9") (pinfunction "PD5(T1)_9") (pintype "bidirectional"))
    )
    (net (code "139") (name "Net-(TQFP32-PD6(AIN0))") (class "Default")
      (node (ref "JP2") (pin "10") (pinfunction "10_10") (pintype "passive"))
      (node (ref "TQFP32") (pin "10") (pinfunction "PD6(AIN0)_10") (pintype "bidirectional"))
    )
    (net (code "140") (name "Net-(TQFP32-PD7(AIN1))") (class "Default")
      (node (ref "JP2") (pin "11") (pinfunction "11_11") (pintype "passive"))
      (node (ref "TQFP32") (pin "11") (pinfunction "PD7(AIN1)_11") (pintype "bidirectional"))
    )
    (net (code "141") (name "Net-(U1-PB6(XTAL1{slash}TOSC1))") (class "Default")
      (node (ref "C1") (pin "2") (pinfunction "2_2") (pintype "passive"))
      (node (ref "U1") (pin "9") (pinfunction "PB6(XTAL1/TOSC1)_9") (pintype "bidirectional"))
      (node (ref "Y1") (pin "2") (pinfunction "2_2") (pintype "passive"))
    )
    (net (code "142") (name "Net-(U1-PB7(XTAL2{slash}TOSC2))") (class "Default")
      (node (ref "C2") (pin "2") (pinfunction "2_2") (pintype "passive"))
      (node (ref "U1") (pin "10") (pinfunction "PB7(XTAL2/TOSC2)_10") (pintype "bidirectional"))
      (node (ref "Y1") (pin "1") (pinfunction "1_1") (pintype "passive"))
    )
    (net (code "143") (name "unconnected-(JP22-Pad1)") (class "Default")
      (node (ref "JP22") (pin "1") (pinfunction "1_1") (pintype "passive"))
    )
    (net (code "144") (name "unconnected-(JP22-Pad2)") (class "Default")
      (node (ref "JP22") (pin "2") (pinfunction "2_2") (pintype "passive"))
    )
    (net (code "145") (name "unconnected-(JP22-Pad3)") (class "Default")
      (node (ref "JP22") (pin "3") (pinfunction "3_3") (pintype "passive"))
    )
    (net (code "146") (name "unconnected-(JP22-Pad4)") (class "Default")
      (node (ref "JP22") (pin "4") (pinfunction "4_4") (pintype "passive"))
    )
    (net (code "147") (name "unconnected-(JP22-Pad5)") (class "Default")
      (node (ref "JP22") (pin "5") (pinfunction "5_5") (pintype "passive"))
    )
    (net (code "148") (name "unconnected-(JP22-Pad6)") (class "Default")
      (node (ref "JP22") (pin "6") (pinfunction "6_6") (pintype "passive"))
    )
    (net (code "149") (name "unconnected-(JP22-Pad7)") (class "Default")
      (node (ref "JP22") (pin "7") (pinfunction "7_7") (pintype "passive"))
    )
    (net (code "150") (name "unconnected-(JP22-Pad8)") (class "Default")
      (node (ref "JP22") (pin "8") (pinfunction "8_8") (pintype "passive"))
    )
    (net (code "151") (name "unconnected-(JP23-Pad1)") (class "Default")
      (node (ref "JP23") (pin "1") (pinfunction "1_1") (pintype "passive"))
    )
    (net (code "152") (name "unconnected-(JP23-Pad2)") (class "Default")
      (node (ref "JP23") (pin "2") (pinfunction "2_2") (pintype "passive"))
    )
    (net (code "153") (name "unconnected-(JP23-Pad3)") (class "Default")
      (node (ref "JP23") (pin "3") (pinfunction "3_3") (pintype "passive"))
    )
    (net (code "154") (name "unconnected-(JP23-Pad4)") (class "Default")
      (node (ref "JP23") (pin "4") (pinfunction "4_4") (pintype "passive"))
    )
    (net (code "155") (name "unconnected-(JP23-Pad5)") (class "Default")
      (node (ref "JP23") (pin "5") (pinfunction "5_5") (pintype "passive"))
    )
    (net (code "156") (name "unconnected-(JP23-Pad6)") (class "Default")
      (node (ref "JP23") (pin "6") (pinfunction "6_6") (pintype "passive"))
    )
    (net (code "157") (name "unconnected-(JP23-Pad7)") (class "Default")
      (node (ref "JP23") (pin "7") (pinfunction "7_7") (pintype "passive"))
    )
    (net (code "158") (name "unconnected-(JP23-Pad8)") (class "Default")
      (node (ref "JP23") (pin "8") (pinfunction "8_8") (pintype "passive"))
    )
    (net (code "159") (name "unconnected-(JP24-Pad1)") (class "Default")
      (node (ref "JP24") (pin "1") (pinfunction "1_1") (pintype "passive"))
    )
    (net (code "160") (name "unconnected-(JP24-Pad2)") (class "Default")
      (node (ref "JP24") (pin "2") (pinfunction "2_2") (pintype "passive"))
    )
    (net (code "161") (name "unconnected-(JP24-Pad3)") (class "Default")
      (node (ref "JP24") (pin "3") (pinfunction "3_3") (pintype "passive"))
    )
    (net (code "162") (name "unconnected-(JP24-Pad4)") (class "Default")
      (node (ref "JP24") (pin "4") (pinfunction "4_4") (pintype "passive"))
    )
    (net (code "163") (name "unconnected-(JP24-Pad5)") (class "Default")
      (node (ref "JP24") (pin "5") (pinfunction "5_5") (pintype "passive"))
    )
    (net (code "164") (name "unconnected-(JP24-Pad6)") (class "Default")
      (node (ref "JP24") (pin "6") (pinfunction "6_6") (pintype "passive"))
    )
    (net (code "165") (name "unconnected-(JP24-Pad7)") (class "Default")
      (node (ref "JP24") (pin "7") (pinfunction "7_7") (pintype "passive"))
    )
    (net (code "166") (name "unconnected-(JP24-Pad8)") (class "Default")
      (node (ref "JP24") (pin "8") (pinfunction "8_8") (pintype "passive"))
    )
    (net (code "167") (name "unconnected-(JP26-Pad1)") (class "Default")
      (node (ref "JP26") (pin "1") (pinfunction "1_1") (pintype "passive"))
    )
    (net (code "168") (name "unconnected-(JP26-Pad2)") (class "Default")
      (node (ref "JP26") (pin "2") (pinfunction "2_2") (pintype "passive"))
    )
    (net (code "169") (name "unconnected-(JP26-Pad3)") (class "Default")
      (node (ref "JP26") (pin "3") (pinfunction "3_3") (pintype "passive"))
    )
    (net (code "170") (name "unconnected-(JP26-Pad4)") (class "Default")
      (node (ref "JP26") (pin "4") (pinfunction "4_4") (pintype "passive"))
    )
    (net (code "171") (name "unconnected-(JP26-Pad5)") (class "Default")
      (node (ref "JP26") (pin "5") (pinfunction "5_5") (pintype "passive"))
    )
    (net (code "172") (name "unconnected-(JP26-Pad6)") (class "Default")
      (node (ref "JP26") (pin "6") (pinfunction "6_6") (pintype "passive"))
    )
    (net (code "173") (name "unconnected-(JP26-Pad7)") (class "Default")
      (node (ref "JP26") (pin "7") (pinfunction "7_7") (pintype "passive"))
    )
    (net (code "174") (name "unconnected-(JP26-Pad8)") (class "Default")
      (node (ref "JP26") (pin "8") (pinfunction "8_8") (pintype "passive"))
    )
    (net (code "175") (name "unconnected-(JP30-Pad1)") (class "Default")
      (node (ref "JP30") (pin "1") (pinfunction "1_1") (pintype "passive"))
    )
    (net (code "176") (name "unconnected-(JP30-Pad2)") (class "Default")
      (node (ref "JP30") (pin "2") (pinfunction "2_2") (pintype "passive"))
    )
    (net (code "177") (name "unconnected-(JP30-Pad3)") (class "Default")
      (node (ref "JP30") (pin "3") (pinfunction "3_3") (pintype "passive"))
    )
    (net (code "178") (name "unconnected-(JP30-Pad4)") (class "Default")
      (node (ref "JP30") (pin "4") (pinfunction "4_4") (pintype "passive"))
    )
    (net (code "179") (name "unconnected-(JP30-Pad5)") (class "Default")
      (node (ref "JP30") (pin "5") (pinfunction "5_5") (pintype "passive"))
    )
    (net (code "180") (name "unconnected-(JP30-Pad6)") (class "Default")
      (node (ref "JP30") (pin "6") (pinfunction "6_6") (pintype "passive"))
    )
    (net (code "181") (name "unconnected-(JP30-Pad7)") (class "Default")
      (node (ref "JP30") (pin "7") (pinfunction "7_7") (pintype "passive"))
    )
    (net (code "182") (name "unconnected-(JP30-Pad8)") (class "Default")
      (node (ref "JP30") (pin "8") (pinfunction "8_8") (pintype "passive"))
    )
    (net (code "183") (name "unconnected-(JP31-Pad1)") (class "Default")
      (node (ref "JP31") (pin "1") (pinfunction "1_1") (pintype "passive"))
    )
    (net (code "184") (name "unconnected-(JP31-Pad2)") (class "Default")
      (node (ref "JP31") (pin "2") (pinfunction "2_2") (pintype "passive"))
    )
    (net (code "185") (name "unconnected-(JP31-Pad3)") (class "Default")
      (node (ref "JP31") (pin "3") (pinfunction "3_3") (pintype "passive"))
    )
    (net (code "186") (name "unconnected-(JP31-Pad4)") (class "Default")
      (node (ref "JP31") (pin "4") (pinfunction "4_4") (pintype "passive"))
    )
    (net (code "187") (name "unconnected-(JP31-Pad5)") (class "Default")
      (node (ref "JP31") (pin "5") (pinfunction "5_5") (pintype "passive"))
    )
    (net (code "188") (name "unconnected-(JP31-Pad6)") (class "Default")
      (node (ref "JP31") (pin "6") (pinfunction "6_6") (pintype "passive"))
    )
    (net (code "189") (name "unconnected-(JP31-Pad7)") (class "Default")
      (node (ref "JP31") (pin "7") (pinfunction "7_7") (pintype "passive"))
    )
    (net (code "190") (name "unconnected-(JP31-Pad8)") (class "Default")
      (node (ref "JP31") (pin "8") (pinfunction "8_8") (pintype "passive"))
    )
  )
)
